# schematic.net
KiCad netlist of a schematic drawn in EAGLE
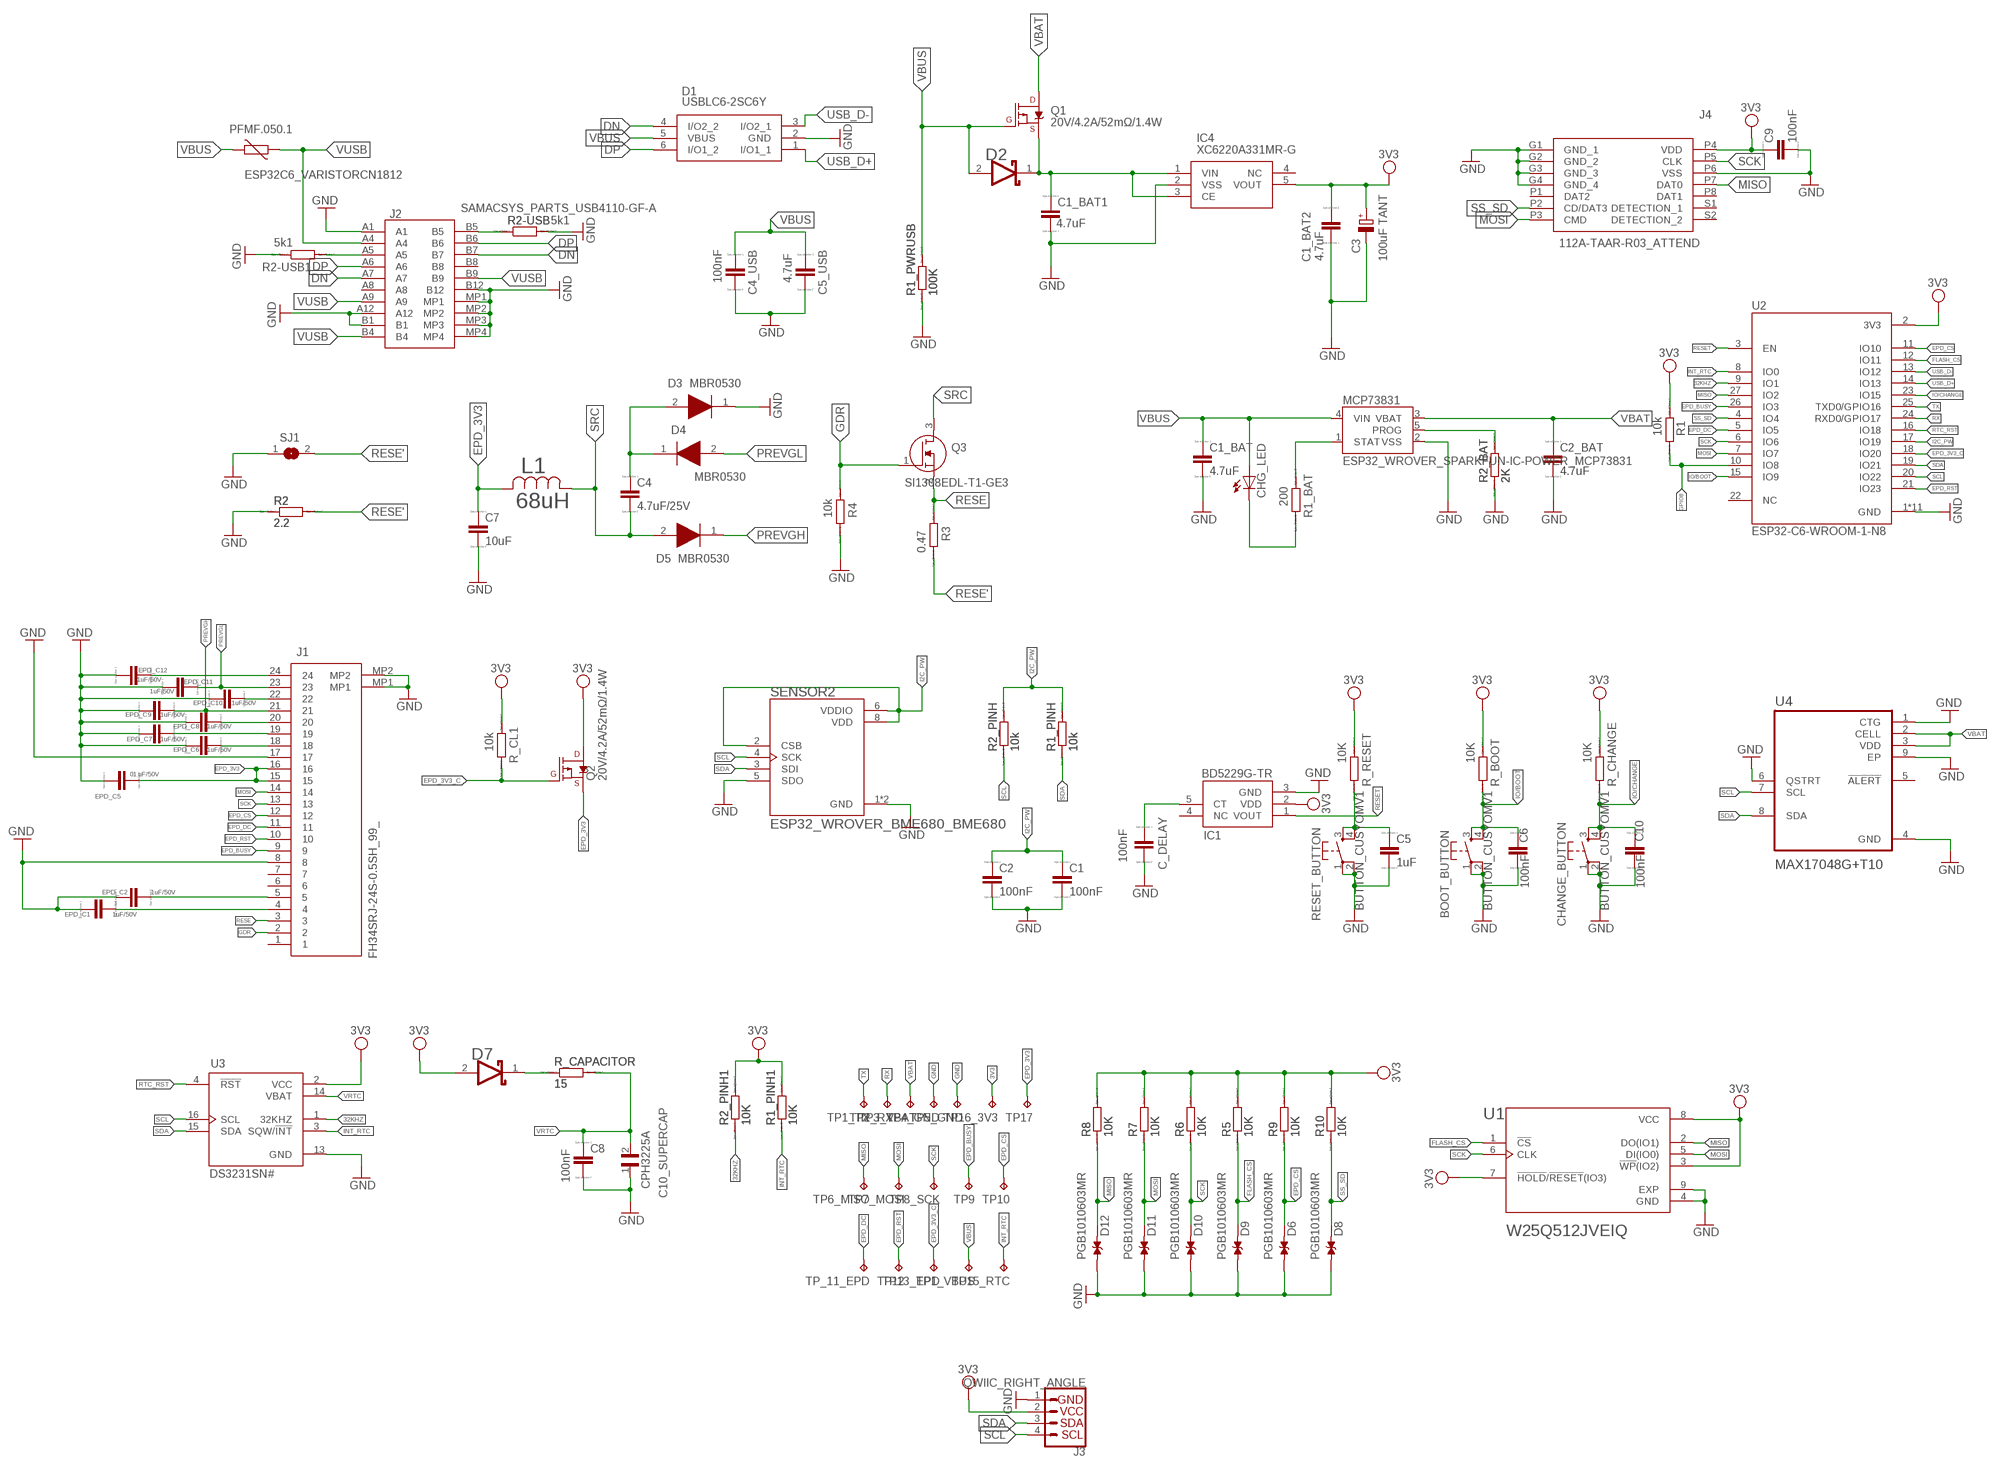
[diagram p0: schematic, sheet 1]

(export (version "E")
  (design (tool "Eeschema 10.0.6"))
  (components
    (comp (ref "BOOT_BUTTON")
      (value "BUTTON_CUSYOMV1")
      (footprint "eagle-import:MYBUTTON")
      (libsource (lib "eagle-import") (part "BUTTON_CUSYOMV1"))
    )
    (comp (ref "C1")
      (value "100nF")
      (footprint "eagle-import:EAGLE-LTSPICE_C0402")
      (libsource (lib "eagle-import") (part "EAGLE-LTSPICE_CC0402"))
    )
    (comp (ref "C1_BAT")
      (value "4.7uF")
      (footprint "eagle-import:EAGLE-LTSPICE_C0402")
      (libsource (lib "eagle-import") (part "EAGLE-LTSPICE_CC0402"))
    )
    (comp (ref "C1_BAT1")
      (value "4.7uF")
      (footprint "eagle-import:EAGLE-LTSPICE_C0402")
      (libsource (lib "eagle-import") (part "ESP32_WROVER_EAGLE-LTSPICE_CC0402"))
    )
    (comp (ref "C1_BAT2")
      (value "4.7uF")
      (footprint "eagle-import:EAGLE-LTSPICE_C0402")
      (libsource (lib "eagle-import") (part "ESP32_WROVER_EAGLE-LTSPICE_CC0402"))
    )
    (comp (ref "C2")
      (value "100nF")
      (footprint "eagle-import:EAGLE-LTSPICE_C0402")
      (libsource (lib "eagle-import") (part "EAGLE-LTSPICE_CC0402"))
    )
    (comp (ref "C2_BAT")
      (value "4.7uF")
      (footprint "eagle-import:EAGLE-LTSPICE_C0402")
      (libsource (lib "eagle-import") (part "EAGLE-LTSPICE_CC0402"))
    )
    (comp (ref "C3")
      (value "100uF TANT")
      (footprint "eagle-import:RCL_CT3528")
      (libsource (lib "eagle-import") (part "RCL_CPOL-EUCT3528"))
    )
    (comp (ref "C4")
      (value "4.7uF/25V")
      (footprint "eagle-import:EAGLE-LTSPICE_C0402")
      (libsource (lib "eagle-import") (part "EAGLE-LTSPICE_CC0402"))
    )
    (comp (ref "C4_USB")
      (value "100nF")
      (footprint "eagle-import:EAGLE-LTSPICE_C0402")
      (libsource (lib "eagle-import") (part "EAGLE-LTSPICE_CC0402"))
    )
    (comp (ref "C5")
      (value "1uF")
      (footprint "eagle-import:EAGLE-LTSPICE_C0402")
      (libsource (lib "eagle-import") (part "EAGLE-LTSPICE_CC0402"))
    )
    (comp (ref "C5_USB")
      (value "4.7uF")
      (footprint "eagle-import:EAGLE-LTSPICE_C0402")
      (libsource (lib "eagle-import") (part "EAGLE-LTSPICE_CC0402"))
    )
    (comp (ref "C6")
      (value "100nF")
      (footprint "eagle-import:EAGLE-LTSPICE_C0402")
      (libsource (lib "eagle-import") (part "EAGLE-LTSPICE_CC0402"))
    )
    (comp (ref "C7")
      (value "10uF")
      (footprint "eagle-import:EAGLE-LTSPICE_C0402")
      (libsource (lib "eagle-import") (part "EAGLE-LTSPICE_CC0402"))
    )
    (comp (ref "C8")
      (value "100nF")
      (footprint "eagle-import:EAGLE-LTSPICE_C0402")
      (libsource (lib "eagle-import") (part "EAGLE-LTSPICE_CC0402"))
    )
    (comp (ref "C9")
      (value "100nF")
      (footprint "eagle-import:EAGLE-LTSPICE_C0402")
      (libsource (lib "eagle-import") (part "EAGLE-LTSPICE_CC0402"))
    )
    (comp (ref "C10")
      (value "100nF")
      (footprint "eagle-import:EAGLE-LTSPICE_C0402")
      (libsource (lib "eagle-import") (part "EAGLE-LTSPICE_CC0402"))
    )
    (comp (ref "C10_SUPERCAP")
      (value "CPH3225A")
      (footprint "eagle-import:CAPCP3225X100N")
      (fields (field (name "MF") "Seiko Instruments"))
      (libsource (lib "eagle-import") (part "CPH3225A"))
    )
    (comp (ref "CHANGE_BUTTON")
      (value "BUTTON_CUSYOMV1")
      (footprint "eagle-import:MYBUTTON")
      (libsource (lib "eagle-import") (part "BUTTON_CUSYOMV1"))
    )
    (comp (ref "CHG_LED")
      (value "ADAFRUIT_LEDCHIP-LED0603")
      (footprint "eagle-import:ADAFRUIT_CHIP-LED0603")
      (libsource (lib "eagle-import") (part "ADAFRUIT_LEDCHIP-LED0603"))
    )
    (comp (ref "C_DELAY")
      (value "100nF")
      (footprint "eagle-import:EAGLE-LTSPICE_C0402")
      (libsource (lib "eagle-import") (part "EAGLE-LTSPICE_CC0402"))
    )
    (comp (ref "D1")
      (value "USBLC6-2SC6Y")
      (footprint "eagle-import:SOT95P280X145-6N")
      (fields (field (name "MF") "STMicroelectronics"))
      (libsource (lib "eagle-import") (part "USBLC6-2SC6Y"))
    )
    (comp (ref "D2")
      (value "ESP32_WROVER_AVX---SD0805S020S1R0_AVX_SD0805S020S1R0_0_0AVX_SD0805S020S1R0_0_0")
      (footprint "eagle-import:ESP32_WROVER_AVX---SD0805S020S1R0_AVX_SD0805S020S1R0_0")
      (fields
        (field (name "DIGIKEY_PART_NUMBER") "478-7800-1-ND")
        (field (name "MF") "AVX")
        (field (name "MOUSER_PART_NUMBER") "581-SD0805S020S1R0")
      )
      (libsource (lib "eagle-import") (part "ESP32_WROVER_AVX---SD0805S020S1R0_AVX_SD0805S020S1R0_0_0AVX_SD0805S020S1R0_0_0"))
    )
    (comp (ref "D3")
      (value "MBR0530")
      (footprint "eagle-import:SOD3716X135N")
      (fields (field (name "MF") "ON Semiconductor"))
      (libsource (lib "eagle-import") (part "MBR0530"))
    )
    (comp (ref "D4")
      (value "MBR0530")
      (footprint "eagle-import:SOD3716X135N")
      (fields (field (name "MF") "ON Semiconductor"))
      (libsource (lib "eagle-import") (part "MBR0530"))
    )
    (comp (ref "D5")
      (value "MBR0530")
      (footprint "eagle-import:SOD3716X135N")
      (fields (field (name "MF") "ON Semiconductor"))
      (libsource (lib "eagle-import") (part "MBR0530"))
    )
    (comp (ref "D6")
      (value "PGB1010603MR")
      (footprint "eagle-import:DIOC1608X36N")
      (fields (field (name "MF") "Littelfuse Inc."))
      (libsource (lib "eagle-import") (part "PGB1010603MR"))
    )
    (comp (ref "D7")
      (value "ESP32_WROVER_AVX---SD0805S020S1R0_AVX_SD0805S020S1R0_0_0AVX_SD0805S020S1R0_0_0")
      (footprint "eagle-import:ESP32_WROVER_AVX---SD0805S020S1R0_AVX_SD0805S020S1R0_0")
      (fields
        (field (name "DIGIKEY_PART_NUMBER") "478-7800-1-ND")
        (field (name "MF") "AVX")
        (field (name "MOUSER_PART_NUMBER") "581-SD0805S020S1R0")
      )
      (libsource (lib "eagle-import") (part "ESP32_WROVER_AVX---SD0805S020S1R0_AVX_SD0805S020S1R0_0_0AVX_SD0805S020S1R0_0_0"))
    )
    (comp (ref "D8")
      (value "PGB1010603MR")
      (footprint "eagle-import:DIOC1608X36N")
      (fields (field (name "MF") "Littelfuse Inc."))
      (libsource (lib "eagle-import") (part "PGB1010603MR"))
    )
    (comp (ref "D9")
      (value "PGB1010603MR")
      (footprint "eagle-import:DIOC1608X36N")
      (fields (field (name "MF") "Littelfuse Inc."))
      (libsource (lib "eagle-import") (part "PGB1010603MR"))
    )
    (comp (ref "D10")
      (value "PGB1010603MR")
      (footprint "eagle-import:DIOC1608X36N")
      (fields (field (name "MF") "Littelfuse Inc."))
      (libsource (lib "eagle-import") (part "PGB1010603MR"))
    )
    (comp (ref "D11")
      (value "PGB1010603MR")
      (footprint "eagle-import:DIOC1608X36N")
      (fields (field (name "MF") "Littelfuse Inc."))
      (libsource (lib "eagle-import") (part "PGB1010603MR"))
    )
    (comp (ref "D12")
      (value "PGB1010603MR")
      (footprint "eagle-import:DIOC1608X36N")
      (fields (field (name "MF") "Littelfuse Inc."))
      (libsource (lib "eagle-import") (part "PGB1010603MR"))
    )
    (comp (ref "EPD_C1")
      (value "1uF/50V")
      (footprint "eagle-import:EAGLE-LTSPICE_C0402")
      (libsource (lib "eagle-import") (part "EAGLE-LTSPICE_CC0402"))
    )
    (comp (ref "EPD_C2")
      (value "1uF/50V")
      (footprint "eagle-import:EAGLE-LTSPICE_C0402")
      (libsource (lib "eagle-import") (part "EAGLE-LTSPICE_CC0402"))
    )
    (comp (ref "EPD_C5")
      (value "01.uF/50V")
      (footprint "eagle-import:EAGLE-LTSPICE_C0402")
      (libsource (lib "eagle-import") (part "EAGLE-LTSPICE_CC0402"))
    )
    (comp (ref "EPD_C6")
      (value "1uF/50V")
      (footprint "eagle-import:EAGLE-LTSPICE_C0402")
      (libsource (lib "eagle-import") (part "EAGLE-LTSPICE_CC0402"))
    )
    (comp (ref "EPD_C7")
      (value "1uF/50V")
      (footprint "eagle-import:EAGLE-LTSPICE_C0402")
      (libsource (lib "eagle-import") (part "EAGLE-LTSPICE_CC0402"))
    )
    (comp (ref "EPD_C8")
      (value "1uF/50V")
      (footprint "eagle-import:EAGLE-LTSPICE_C0402")
      (libsource (lib "eagle-import") (part "EAGLE-LTSPICE_CC0402"))
    )
    (comp (ref "EPD_C9")
      (value "1uF/50V")
      (footprint "eagle-import:EAGLE-LTSPICE_C0402")
      (libsource (lib "eagle-import") (part "EAGLE-LTSPICE_CC0402"))
    )
    (comp (ref "EPD_C10")
      (value "1uF/50V")
      (footprint "eagle-import:EAGLE-LTSPICE_C0402")
      (libsource (lib "eagle-import") (part "EAGLE-LTSPICE_CC0402"))
    )
    (comp (ref "EPD_C11")
      (value "1uF/50V")
      (footprint "eagle-import:EAGLE-LTSPICE_C0402")
      (libsource (lib "eagle-import") (part "EAGLE-LTSPICE_CC0402"))
    )
    (comp (ref "EPD_C12")
      (value "1uF/50V")
      (footprint "eagle-import:EAGLE-LTSPICE_C0402")
      (libsource (lib "eagle-import") (part "EAGLE-LTSPICE_CC0402"))
    )
    (comp (ref "IC1")
      (value "BD5229G-TR")
      (footprint "eagle-import:SOT95P280X125-5N")
      (fields (field (name "MOUSER_PART_NUMBER") "755-BD5229G-TR"))
      (libsource (lib "eagle-import") (part "BD5229G-TR"))
    )
    (comp (ref "IC4")
      (value "XC6220A331MR-G")
      (footprint "eagle-import:SOT95P280X120-5N")
      (fields (field (name "MOUSER_PART_NUMBER") "865-XC6220A331MR-G"))
      (libsource (lib "eagle-import") (part "XC6220A331MR-G"))
    )
    (comp (ref "J1")
      (value "FH34SRJ-24S-0.5SH_99_")
      (footprint "eagle-import:FH34SRJ24S05SH99")
      (fields
        (field (name "MANUFACTURER_PART_NUMBER") "FH34SRJ-24S-0.5SH(99)")
        (field (name "MOUSER_PART_NUMBER") "798-FH34SRJ24S05SH99")
      )
      (libsource (lib "eagle-import") (part "FH34SRJ-24S-0.5SH_99_"))
    )
    (comp (ref "J2")
      (value "SAMACSYS_PARTS_USB4110-GF-A")
      (footprint "eagle-import:SAMACSYS_PARTS_USB4110GFA")
      (fields
        (field (name "MANUFACTURER_PART_NUMBER") "USB4110-GF-A")
        (field (name "MOUSER_PART_NUMBER") "640-USB4110-GF-A")
      )
      (libsource (lib "eagle-import") (part "SAMACSYS_PARTS_USB4110-GF-A"))
    )
    (comp (ref "J3")
      (value "QWIIC_RIGHT_ANGLE")
      (footprint "eagle-import:JST04_1MM_RA")
      (libsource (lib "eagle-import") (part "QWIIC_CONNECTORJS-1MM"))
    )
    (comp (ref "J4")
      (value "112A-TAAR-R03_ATTEND")
      (footprint "eagle-import:112ATAARR03ATTEND")
      (fields (field (name "MANUFACTURER_PART_NUMBER") "112A-TAAR-R03 ATTEND"))
      (libsource (lib "eagle-import") (part "112A-TAAR-R03_ATTEND"))
    )
    (comp (ref "L1")
      (value "68uH")
      (footprint "eagle-import:IND_4828-WE-TPC_WRE")
      (fields
        (field (name "MANUFACTURER_PART_NUMBER") "744043680")
        (field (name "COPYRIGHT") "Copyright (C) 2024 Ultra Librarian. All rights reserved.")
      )
      (libsource (lib "eagle-import") (part "744043680IND_4828-WE-TPC_WRE"))
    )
    (comp (ref "MCP73831")
      (value "ESP32_WROVER_SPARKFUN-IC-POWER_MCP73831")
      (footprint "eagle-import:ESP32_WROVER_SPARKFUN-IC-POWER_SOT23-5")
      (libsource (lib "eagle-import") (part "ESP32_WROVER_SPARKFUN-IC-POWER_MCP73831"))
    )
    (comp (ref "PFMF.050.1")
      (value "ESP32C6_VARISTORCN1812")
      (footprint "eagle-import:ESP32C6_VARISTOR_CT_CN1812")
      (libsource (lib "eagle-import") (part "ESP32C6_VARISTORCN1812"))
    )
    (comp (ref "Q1")
      (value "20V/4.2A/52mΩ/1.4W")
      (footprint "eagle-import:ESP32_WROVER_SPARKFUN-DISCRETESEMI_SOT23-3")
      (libsource (lib "eagle-import") (part "ESP32_WROVER_SPARKFUN-DISCRETESEMI_MOSFET_PCH-DMG2305UX-7"))
    )
    (comp (ref "Q2")
      (value "20V/4.2A/52mΩ/1.4W")
      (footprint "eagle-import:ESP32_WROVER_SPARKFUN-DISCRETESEMI_SOT23-3")
      (libsource (lib "eagle-import") (part "ESP32_WROVER_SPARKFUN-DISCRETESEMI_MOSFET_PCH-DMG2305UX-7"))
    )
    (comp (ref "Q3")
      (value "SI1308EDL-T1-GE3")
      (footprint "eagle-import:SOT65P210X110-3N")
      (fields (field (name "MF") "Vishay Siliconix"))
      (libsource (lib "eagle-import") (part "SI1308EDL-T1-GE3"))
    )
    (comp (ref "R1")
      (value "10k")
      (footprint "eagle-import:ESP32_WROVER_EAGLE-LTSPICE_R0402")
      (libsource (lib "eagle-import") (part "ESP32_WROVER_EAGLE-LTSPICE_RR0402"))
    )
    (comp (ref "R1_BAT")
      (value "200")
      (footprint "eagle-import:ESP32_WROVER_EAGLE-LTSPICE_R0402")
      (libsource (lib "eagle-import") (part "ESP32_WROVER_EAGLE-LTSPICE_RR0402"))
    )
    (comp (ref "R1_PINH")
      (value "10k")
      (footprint "eagle-import:ESP32_WROVER_EAGLE-LTSPICE_R0402")
      (libsource (lib "eagle-import") (part "ESP32_WROVER_EAGLE-LTSPICE_RR0402"))
    )
    (comp (ref "R1_PINH1")
      (value "10K")
      (footprint "eagle-import:ESP32_WROVER_EAGLE-LTSPICE_R0402")
      (libsource (lib "eagle-import") (part "ESP32_WROVER_EAGLE-LTSPICE_RR0402"))
    )
    (comp (ref "R1_PWRUSB")
      (value "100K")
      (footprint "eagle-import:ESP32_WROVER_EAGLE-LTSPICE_R0402")
      (libsource (lib "eagle-import") (part "ESP32_WROVER_EAGLE-LTSPICE_RR0402"))
    )
    (comp (ref "R2")
      (value "2.2")
      (footprint "eagle-import:ESP32_WROVER_EAGLE-LTSPICE_R0402")
      (libsource (lib "eagle-import") (part "ESP32_WROVER_EAGLE-LTSPICE_RR0402"))
    )
    (comp (ref "R2-USB")
      (value "5k1")
      (footprint "eagle-import:ESP32_WROVER_EAGLE-LTSPICE_R0402")
      (libsource (lib "eagle-import") (part "ESP32_WROVER_EAGLE-LTSPICE_RR0402"))
    )
    (comp (ref "R2-USB1")
      (value "5k1")
      (footprint "eagle-import:ESP32_WROVER_EAGLE-LTSPICE_R0402")
      (libsource (lib "eagle-import") (part "ESP32_WROVER_EAGLE-LTSPICE_RR0402"))
    )
    (comp (ref "R2_BAT")
      (value "2K")
      (footprint "eagle-import:ESP32_WROVER_EAGLE-LTSPICE_R0402")
      (libsource (lib "eagle-import") (part "ESP32_WROVER_EAGLE-LTSPICE_RR0402"))
    )
    (comp (ref "R2_PINH")
      (value "10k")
      (footprint "eagle-import:ESP32_WROVER_EAGLE-LTSPICE_R0402")
      (libsource (lib "eagle-import") (part "ESP32_WROVER_EAGLE-LTSPICE_RR0402"))
    )
    (comp (ref "R2_PINH1")
      (value "10K")
      (footprint "eagle-import:ESP32_WROVER_EAGLE-LTSPICE_R0402")
      (libsource (lib "eagle-import") (part "ESP32_WROVER_EAGLE-LTSPICE_RR0402"))
    )
    (comp (ref "R3")
      (value "0.47")
      (footprint "eagle-import:ESP32_WROVER_EAGLE-LTSPICE_R0402")
      (libsource (lib "eagle-import") (part "ESP32_WROVER_EAGLE-LTSPICE_RR0402"))
    )
    (comp (ref "R4")
      (value "10k")
      (footprint "eagle-import:ESP32_WROVER_EAGLE-LTSPICE_R0402")
      (libsource (lib "eagle-import") (part "ESP32_WROVER_EAGLE-LTSPICE_RR0402"))
    )
    (comp (ref "R5")
      (value "10K")
      (footprint "eagle-import:ESP32_WROVER_EAGLE-LTSPICE_R0402")
      (libsource (lib "eagle-import") (part "ESP32_WROVER_EAGLE-LTSPICE_RR0402"))
    )
    (comp (ref "R6")
      (value "10K")
      (footprint "eagle-import:ESP32_WROVER_EAGLE-LTSPICE_R0402")
      (libsource (lib "eagle-import") (part "ESP32_WROVER_EAGLE-LTSPICE_RR0402"))
    )
    (comp (ref "R7")
      (value "10K")
      (footprint "eagle-import:ESP32_WROVER_EAGLE-LTSPICE_R0402")
      (libsource (lib "eagle-import") (part "ESP32_WROVER_EAGLE-LTSPICE_RR0402"))
    )
    (comp (ref "R8")
      (value "10K")
      (footprint "eagle-import:ESP32_WROVER_EAGLE-LTSPICE_R0402")
      (libsource (lib "eagle-import") (part "ESP32_WROVER_EAGLE-LTSPICE_RR0402"))
    )
    (comp (ref "R9")
      (value "10K")
      (footprint "eagle-import:ESP32_WROVER_EAGLE-LTSPICE_R0402")
      (libsource (lib "eagle-import") (part "ESP32_WROVER_EAGLE-LTSPICE_RR0402"))
    )
    (comp (ref "R10")
      (value "10K")
      (footprint "eagle-import:ESP32_WROVER_EAGLE-LTSPICE_R0402")
      (libsource (lib "eagle-import") (part "ESP32_WROVER_EAGLE-LTSPICE_RR0402"))
    )
    (comp (ref "RESET_BUTTON")
      (value "BUTTON_CUSYOMV1")
      (footprint "eagle-import:MYBUTTON")
      (libsource (lib "eagle-import") (part "BUTTON_CUSYOMV1"))
    )
    (comp (ref "R_BOOT")
      (value "10K")
      (footprint "eagle-import:ESP32_WROVER_EAGLE-LTSPICE_R0402")
      (libsource (lib "eagle-import") (part "ESP32_WROVER_EAGLE-LTSPICE_RR0402"))
    )
    (comp (ref "R_CAPACITOR")
      (value "15")
      (footprint "eagle-import:ESP32_WROVER_EAGLE-LTSPICE_R0402")
      (libsource (lib "eagle-import") (part "ESP32_WROVER_EAGLE-LTSPICE_RR0402"))
    )
    (comp (ref "R_CHANGE")
      (value "10K")
      (footprint "eagle-import:ESP32_WROVER_EAGLE-LTSPICE_R0402")
      (libsource (lib "eagle-import") (part "ESP32_WROVER_EAGLE-LTSPICE_RR0402"))
    )
    (comp (ref "R_CL1")
      (value "10k")
      (footprint "eagle-import:ESP32_WROVER_EAGLE-LTSPICE_R0402")
      (libsource (lib "eagle-import") (part "ESP32_WROVER_EAGLE-LTSPICE_RR0402"))
    )
    (comp (ref "R_RESET")
      (value "10K")
      (footprint "eagle-import:ESP32_WROVER_EAGLE-LTSPICE_R0402")
      (libsource (lib "eagle-import") (part "ESP32_WROVER_EAGLE-LTSPICE_RR0402"))
    )
    (comp (ref "SENSOR2")
      (value "ESP32_WROVER_BME680_BME680")
      (footprint "eagle-import:ESP32_WROVER_BME680_PSON80P300X300X100-8N")
      (fields (field (name "MF") "Bosch Sensortec") (field (name "MP") "BME680"))
      (libsource (lib "eagle-import") (part "ESP32_WROVER_BME680_BME680"))
    )
    (comp (ref "SJ1") (value "SJ") (footprint "eagle-import:SJ") (libsource (lib "eagle-import") (part "SJ")))
    (comp (ref "TP1_TX")
      (value "TPTP20R")
      (footprint "eagle-import:TP20R")
      (libsource (lib "eagle-import") (part "TPTP20R"))
    )
    (comp (ref "TP1_VBUS")
      (value "TPTP20R")
      (footprint "eagle-import:TP20R")
      (libsource (lib "eagle-import") (part "TPTP20R"))
    )
    (comp (ref "TP2_RX")
      (value "TPTP20R")
      (footprint "eagle-import:TP20R")
      (libsource (lib "eagle-import") (part "TPTP20R"))
    )
    (comp (ref "TP3_VBAT")
      (value "TPTP20R")
      (footprint "eagle-import:TP20R")
      (libsource (lib "eagle-import") (part "TPTP20R"))
    )
    (comp (ref "TP4_GND")
      (value "TPTP20R")
      (footprint "eagle-import:TP20R")
      (libsource (lib "eagle-import") (part "TPTP20R"))
    )
    (comp (ref "TP5_GND")
      (value "TPTP20R")
      (footprint "eagle-import:TP20R")
      (libsource (lib "eagle-import") (part "TPTP20R"))
    )
    (comp (ref "TP6_MISO")
      (value "TPTP20R")
      (footprint "eagle-import:TP20R")
      (libsource (lib "eagle-import") (part "TPTP20R"))
    )
    (comp (ref "TP7_MOSI")
      (value "TPTP20R")
      (footprint "eagle-import:TP20R")
      (libsource (lib "eagle-import") (part "TPTP20R"))
    )
    (comp (ref "TP8_SCK")
      (value "TPTP20R")
      (footprint "eagle-import:TP20R")
      (libsource (lib "eagle-import") (part "TPTP20R"))
    )
    (comp (ref "TP9")
      (value "TPTP20R")
      (footprint "eagle-import:TP20R")
      (libsource (lib "eagle-import") (part "TPTP20R"))
    )
    (comp (ref "TP10")
      (value "TPTP20R")
      (footprint "eagle-import:TP20R")
      (libsource (lib "eagle-import") (part "TPTP20R"))
    )
    (comp (ref "TP12")
      (value "TPTP20R")
      (footprint "eagle-import:TP20R")
      (libsource (lib "eagle-import") (part "TPTP20R"))
    )
    (comp (ref "TP13_EPD")
      (value "TPTP20R")
      (footprint "eagle-import:TP20R")
      (libsource (lib "eagle-import") (part "TPTP20R"))
    )
    (comp (ref "TP15_RTC")
      (value "TPTP20R")
      (footprint "eagle-import:TP20R")
      (libsource (lib "eagle-import") (part "TPTP20R"))
    )
    (comp (ref "TP16_3V3")
      (value "TPTP20R")
      (footprint "eagle-import:TP20R")
      (libsource (lib "eagle-import") (part "TPTP20R"))
    )
    (comp (ref "TP17")
      (value "TPTP20R")
      (footprint "eagle-import:TP20R")
      (libsource (lib "eagle-import") (part "TPTP20R"))
    )
    (comp (ref "TP_11_EPD")
      (value "TPTP20R")
      (footprint "eagle-import:TP20R")
      (libsource (lib "eagle-import") (part "TPTP20R"))
    )
    (comp (ref "U1")
      (value "W25Q512JVEIQ")
      (footprint "eagle-import:SON127P600X800X80-9N")
      (fields (field (name "MF") "Winbond Electronics"))
      (libsource (lib "eagle-import") (part "W25Q512JVEIQ"))
    )
    (comp (ref "U2")
      (value "ESP32-C6-WROOM-1-N8")
      (footprint "eagle-import:XCVR_ESP32-C6-WROOM-1-N8")
      (fields (field (name "MF") "Espressif Systems"))
      (libsource (lib "eagle-import") (part "ESP32-C6-WROOM-1-N8"))
    )
    (comp (ref "U3")
      (value "DS3231SN#")
      (footprint "eagle-import:SOIC127P1032X265-16N")
      (fields (field (name "MF") "Analog Devices"))
      (libsource (lib "eagle-import") (part "DS3231SN#"))
    )
    (comp (ref "U4")
      (value "MAX17048G+T10")
      (footprint "eagle-import:SON50P200X200X80-9N")
      (fields (field (name "MF") "Analog Devices"))
      (libsource (lib "eagle-import") (part "MAX17048G+T10"))
    )
  )
  (nets
    (net (code "1") (name "3V3") (class "Default")
      (node (ref "C1_BAT2") (pin "2") (pinfunction "2_2") (pintype "passive"))
      (node (ref "C3") (pin "+") (pinfunction "+_+") (pintype "passive"))
      (node (ref "C9") (pin "1") (pinfunction "1_1") (pintype "passive"))
      (node (ref "D7") (pin "2") (pinfunction "ANODE_2") (pintype "bidirectional"))
      (node (ref "IC1") (pin "2") (pinfunction "VDD_2") (pintype "bidirectional"))
      (node (ref "IC4") (pin "5") (pinfunction "VOUT_5") (pintype "bidirectional"))
      (node (ref "J3") (pin "2") (pinfunction "2_2") (pintype "power_in"))
      (node (ref "J4") (pin "P4") (pinfunction "VDD_P4") (pintype "bidirectional"))
      (node (ref "Q2") (pin "3") (pinfunction "D_3") (pintype "bidirectional"))
      (node (ref "R1") (pin "2") (pinfunction "2_2") (pintype "passive"))
      (node (ref "R10") (pin "2") (pinfunction "2_2") (pintype "passive"))
      (node (ref "R1_PINH1") (pin "2") (pinfunction "2_2") (pintype "passive"))
      (node (ref "R2_PINH1") (pin "2") (pinfunction "2_2") (pintype "passive"))
      (node (ref "R5") (pin "2") (pinfunction "2_2") (pintype "passive"))
      (node (ref "R6") (pin "2") (pinfunction "2_2") (pintype "passive"))
      (node (ref "R7") (pin "2") (pinfunction "2_2") (pintype "passive"))
      (node (ref "R8") (pin "2") (pinfunction "2_2") (pintype "passive"))
      (node (ref "R9") (pin "2") (pinfunction "2_2") (pintype "passive"))
      (node (ref "R_BOOT") (pin "2") (pinfunction "2_2") (pintype "passive"))
      (node (ref "R_CHANGE") (pin "2") (pinfunction "2_2") (pintype "passive"))
      (node (ref "R_CL1") (pin "2") (pinfunction "2_2") (pintype "passive"))
      (node (ref "R_RESET") (pin "2") (pinfunction "2_2") (pintype "passive"))
      (node (ref "TP16_3V3") (pin "TP") (pinfunction "TP_TP") (pintype "input"))
      (node (ref "U1") (pin "3") (pinfunction "~{WP}(IO2)_3") (pintype "bidirectional"))
      (node (ref "U1") (pin "7") (pinfunction "~{HOLD}/~{RESET}(IO3)_7") (pintype "bidirectional"))
      (node (ref "U1") (pin "8") (pinfunction "VCC_8") (pintype "power_in"))
      (node (ref "U2") (pin "2") (pinfunction "3V3_2") (pintype "power_in"))
      (node (ref "U3") (pin "2") (pinfunction "VCC_2") (pintype "power_in"))
    )
    (net (code "2") (name "32KHZ") (class "Default")
      (node (ref "R2_PINH1") (pin "1") (pinfunction "1_1") (pintype "passive"))
      (node (ref "U2") (pin "9") (pinfunction "IO1_9") (pintype "bidirectional"))
      (node (ref "U3") (pin "1") (pinfunction "32KHZ_1") (pintype "output"))
    )
    (net (code "3") (name "DN") (class "Default")
      (node (ref "D1") (pin "4") (pinfunction "I/O2_2_4") (pintype "bidirectional"))
      (node (ref "J2") (pin "A7") (pinfunction "A7_A7") (pintype "bidirectional"))
      (node (ref "J2") (pin "B7") (pinfunction "B7_B7") (pintype "bidirectional"))
    )
    (net (code "4") (name "DP") (class "Default")
      (node (ref "D1") (pin "6") (pinfunction "I/O1_2_6") (pintype "bidirectional"))
      (node (ref "J2") (pin "A6") (pinfunction "A6_A6") (pintype "bidirectional"))
      (node (ref "J2") (pin "B6") (pinfunction "B6_B6") (pintype "bidirectional"))
    )
    (net (code "5") (name "EPD_3V3") (class "Default")
      (node (ref "C7") (pin "1") (pinfunction "1_1") (pintype "passive"))
      (node (ref "EPD_C5") (pin "2") (pinfunction "2_2") (pintype "passive"))
      (node (ref "J1") (pin "15") (pinfunction "15_15") (pintype "bidirectional"))
      (node (ref "J1") (pin "16") (pinfunction "16_16") (pintype "bidirectional"))
      (node (ref "L1") (pin "2") (pinfunction "2_2") (pintype "passive"))
      (node (ref "Q2") (pin "2") (pinfunction "S_2") (pintype "bidirectional"))
      (node (ref "TP17") (pin "TP") (pinfunction "TP_TP") (pintype "input"))
    )
    (net (code "6") (name "EPD_3V3_C") (class "Default")
      (node (ref "Q2") (pin "1") (pinfunction "G_1") (pintype "bidirectional"))
      (node (ref "R_CL1") (pin "1") (pinfunction "1_1") (pintype "passive"))
      (node (ref "TP13_EPD") (pin "TP") (pinfunction "TP_TP") (pintype "input"))
      (node (ref "U2") (pin "18") (pinfunction "IO20_18") (pintype "bidirectional"))
    )
    (net (code "7") (name "EPD_BUSY") (class "Default")
      (node (ref "J1") (pin "9") (pinfunction "9_9") (pintype "bidirectional"))
      (node (ref "TP9") (pin "TP") (pinfunction "TP_TP") (pintype "input"))
      (node (ref "U2") (pin "26") (pinfunction "IO3_26") (pintype "bidirectional"))
    )
    (net (code "8") (name "EPD_CS") (class "Default")
      (node (ref "D6") (pin "2") (pinfunction "2_2") (pintype "passive"))
      (node (ref "J1") (pin "12") (pinfunction "12_12") (pintype "bidirectional"))
      (node (ref "R9") (pin "1") (pinfunction "1_1") (pintype "passive"))
      (node (ref "TP10") (pin "TP") (pinfunction "TP_TP") (pintype "input"))
      (node (ref "U2") (pin "11") (pinfunction "IO10_11") (pintype "bidirectional"))
    )
    (net (code "9") (name "EPD_DC") (class "Default")
      (node (ref "J1") (pin "11") (pinfunction "11_11") (pintype "bidirectional"))
      (node (ref "TP_11_EPD") (pin "TP") (pinfunction "TP_TP") (pintype "input"))
      (node (ref "U2") (pin "5") (pinfunction "IO5_5") (pintype "bidirectional"))
    )
    (net (code "10") (name "EPD_RST") (class "Default")
      (node (ref "J1") (pin "10") (pinfunction "10_10") (pintype "bidirectional"))
      (node (ref "TP12") (pin "TP") (pinfunction "TP_TP") (pintype "input"))
      (node (ref "U2") (pin "21") (pinfunction "IO23_21") (pintype "bidirectional"))
    )
    (net (code "11") (name "FLASH_CS") (class "Default")
      (node (ref "D9") (pin "2") (pinfunction "2_2") (pintype "passive"))
      (node (ref "R5") (pin "1") (pinfunction "1_1") (pintype "passive"))
      (node (ref "U1") (pin "1") (pinfunction "~{CS}_1") (pintype "input"))
      (node (ref "U2") (pin "12") (pinfunction "IO11_12") (pintype "bidirectional"))
    )
    (net (code "12") (name "GDR") (class "Default")
      (node (ref "J1") (pin "2") (pinfunction "2_2") (pintype "bidirectional"))
      (node (ref "Q3") (pin "1") (pinfunction "G_1") (pintype "bidirectional"))
      (node (ref "R4") (pin "2") (pinfunction "2_2") (pintype "passive"))
    )
    (net (code "13") (name "GND") (class "Default")
      (node (ref "BOOT_BUTTON") (pin "1") (pinfunction "1_1") (pintype "passive"))
      (node (ref "BOOT_BUTTON") (pin "2") (pinfunction "2_2") (pintype "passive"))
      (node (ref "C1") (pin "2") (pinfunction "2_2") (pintype "passive"))
      (node (ref "C10") (pin "2") (pinfunction "2_2") (pintype "passive"))
      (node (ref "C10_SUPERCAP") (pin "1") (pinfunction "1_1") (pintype "passive"))
      (node (ref "C1_BAT") (pin "2") (pinfunction "2_2") (pintype "passive"))
      (node (ref "C1_BAT1") (pin "1") (pinfunction "1_1") (pintype "passive"))
      (node (ref "C1_BAT2") (pin "1") (pinfunction "1_1") (pintype "passive"))
      (node (ref "C2") (pin "2") (pinfunction "2_2") (pintype "passive"))
      (node (ref "C2_BAT") (pin "2") (pinfunction "2_2") (pintype "passive"))
      (node (ref "C3") (pin "-") (pinfunction "-_-") (pintype "passive"))
      (node (ref "C4_USB") (pin "2") (pinfunction "2_2") (pintype "passive"))
      (node (ref "C5") (pin "2") (pinfunction "2_2") (pintype "passive"))
      (node (ref "C5_USB") (pin "2") (pinfunction "2_2") (pintype "passive"))
      (node (ref "C6") (pin "2") (pinfunction "2_2") (pintype "passive"))
      (node (ref "C7") (pin "2") (pinfunction "2_2") (pintype "passive"))
      (node (ref "C8") (pin "2") (pinfunction "2_2") (pintype "passive"))
      (node (ref "C9") (pin "2") (pinfunction "2_2") (pintype "passive"))
      (node (ref "CHANGE_BUTTON") (pin "1") (pinfunction "1_1") (pintype "passive"))
      (node (ref "CHANGE_BUTTON") (pin "2") (pinfunction "2_2") (pintype "passive"))
      (node (ref "C_DELAY") (pin "2") (pinfunction "2_2") (pintype "passive"))
      (node (ref "D1") (pin "2") (pinfunction "GND_2") (pintype "bidirectional"))
      (node (ref "D10") (pin "1") (pinfunction "1_1") (pintype "passive"))
      (node (ref "D11") (pin "1") (pinfunction "1_1") (pintype "passive"))
      (node (ref "D12") (pin "1") (pinfunction "1_1") (pintype "passive"))
      (node (ref "D3") (pin "1") (pinfunction "K_1") (pintype "bidirectional"))
      (node (ref "D6") (pin "1") (pinfunction "1_1") (pintype "passive"))
      (node (ref "D8") (pin "1") (pinfunction "1_1") (pintype "passive"))
      (node (ref "D9") (pin "1") (pinfunction "1_1") (pintype "passive"))
      (node (ref "EPD_C1") (pin "1") (pinfunction "1_1") (pintype "passive"))
      (node (ref "EPD_C10") (pin "1") (pinfunction "1_1") (pintype "passive"))
      (node (ref "EPD_C11") (pin "1") (pinfunction "1_1") (pintype "passive"))
      (node (ref "EPD_C12") (pin "1") (pinfunction "1_1") (pintype "passive"))
      (node (ref "EPD_C2") (pin "1") (pinfunction "1_1") (pintype "passive"))
      (node (ref "EPD_C5") (pin "1") (pinfunction "1_1") (pintype "passive"))
      (node (ref "EPD_C6") (pin "1") (pinfunction "1_1") (pintype "passive"))
      (node (ref "EPD_C7") (pin "1") (pinfunction "1_1") (pintype "passive"))
      (node (ref "EPD_C8") (pin "1") (pinfunction "1_1") (pintype "passive"))
      (node (ref "EPD_C9") (pin "1") (pinfunction "1_1") (pintype "passive"))
      (node (ref "IC1") (pin "3") (pinfunction "GND_3") (pintype "bidirectional"))
      (node (ref "IC4") (pin "2") (pinfunction "VSS_2") (pintype "bidirectional"))
      (node (ref "J1") (pin "17") (pinfunction "17_17") (pintype "bidirectional"))
      (node (ref "J1") (pin "8") (pinfunction "8_8") (pintype "bidirectional"))
      (node (ref "J1") (pin "MP1") (pinfunction "MP1_MP1") (pintype "bidirectional"))
      (node (ref "J1") (pin "MP2") (pinfunction "MP2_MP2") (pintype "bidirectional"))
      (node (ref "J2") (pin "A1") (pinfunction "A1_A1") (pintype "bidirectional"))
      (node (ref "J2") (pin "A12") (pinfunction "A12_A12") (pintype "bidirectional"))
      (node (ref "J2") (pin "B1") (pinfunction "B1_B1") (pintype "bidirectional"))
      (node (ref "J2") (pin "B12") (pinfunction "B12_B12") (pintype "bidirectional"))
      (node (ref "J2") (pin "MP1") (pinfunction "MP1_MP1") (pintype "bidirectional"))
      (node (ref "J2") (pin "MP2") (pinfunction "MP2_MP2") (pintype "bidirectional"))
      (node (ref "J2") (pin "MP3") (pinfunction "MP3_MP3") (pintype "bidirectional"))
      (node (ref "J2") (pin "MP4") (pinfunction "MP4_MP4") (pintype "bidirectional"))
      (node (ref "J3") (pin "1") (pinfunction "1_1") (pintype "power_in"))
      (node (ref "J4") (pin "G1") (pinfunction "GND_1_G1") (pintype "bidirectional"))
      (node (ref "J4") (pin "G2") (pinfunction "GND_2_G2") (pintype "bidirectional"))
      (node (ref "J4") (pin "G3") (pinfunction "GND_3_G3") (pintype "bidirectional"))
      (node (ref "J4") (pin "G4") (pinfunction "GND_4_G4") (pintype "bidirectional"))
      (node (ref "J4") (pin "P6") (pinfunction "VSS_P6") (pintype "bidirectional"))
      (node (ref "MCP73831") (pin "2") (pinfunction "VSS_2") (pintype "power_in"))
      (node (ref "R1_PWRUSB") (pin "1") (pinfunction "1_1") (pintype "passive"))
      (node (ref "R2") (pin "1") (pinfunction "1_1") (pintype "passive"))
      (node (ref "R2-USB") (pin "2") (pinfunction "2_2") (pintype "passive"))
      (node (ref "R2-USB1") (pin "1") (pinfunction "1_1") (pintype "passive"))
      (node (ref "R2_BAT") (pin "1") (pinfunction "1_1") (pintype "passive"))
      (node (ref "R4") (pin "1") (pinfunction "1_1") (pintype "passive"))
      (node (ref "RESET_BUTTON") (pin "1") (pinfunction "1_1") (pintype "passive"))
      (node (ref "RESET_BUTTON") (pin "2") (pinfunction "2_2") (pintype "passive"))
      (node (ref "SENSOR2") (pin "1") (pinfunction "GND_1") (pintype "power_in"))
      (node (ref "SENSOR2") (pin "5") (pinfunction "SDO_5") (pintype "bidirectional"))
      (node (ref "SENSOR2") (pin "7") (pinfunction "GND_7") (pintype "power_in"))
      (node (ref "SJ1") (pin "1") (pinfunction "1_1") (pintype "passive"))
      (node (ref "TP4_GND") (pin "TP") (pinfunction "TP_TP") (pintype "input"))
      (node (ref "TP5_GND") (pin "TP") (pinfunction "TP_TP") (pintype "input"))
      (node (ref "U1") (pin "4") (pinfunction "GND_4") (pintype "power_in"))
      (node (ref "U1") (pin "9") (pinfunction "EXP_9") (pintype "passive"))
      (node (ref "U2") (pin "1") (pinfunction "GND_1") (pintype "power_in"))
      (node (ref "U2") (pin "28") (pinfunction "GND_28") (pintype "power_in"))
      (node (ref "U2") (pin "29_1") (pinfunction "GND_29_1") (pintype "power_in"))
      (node (ref "U2") (pin "29_2") (pinfunction "GND_29_2") (pintype "power_in"))
      (node (ref "U2") (pin "29_3") (pinfunction "GND_29_3") (pintype "power_in"))
      (node (ref "U2") (pin "29_4") (pinfunction "GND_29_4") (pintype "power_in"))
      (node (ref "U2") (pin "29_5") (pinfunction "GND_29_5") (pintype "power_in"))
      (node (ref "U2") (pin "29_6") (pinfunction "GND_29_6") (pintype "power_in"))
      (node (ref "U2") (pin "29_7") (pinfunction "GND_29_7") (pintype "power_in"))
      (node (ref "U2") (pin "29_8") (pinfunction "GND_29_8") (pintype "power_in"))
      (node (ref "U2") (pin "29_9") (pinfunction "GND_29_9") (pintype "power_in"))
      (node (ref "U3") (pin "13") (pinfunction "GND_13") (pintype "power_in"))
      (node (ref "U4") (pin "1") (pinfunction "CTG_1") (pintype "power_in"))
      (node (ref "U4") (pin "4") (pinfunction "GND_4") (pintype "power_in"))
      (node (ref "U4") (pin "6") (pinfunction "QSTRT_6") (pintype "input"))
      (node (ref "U4") (pin "9") (pinfunction "EP_9") (pintype "power_in"))
    )
    (net (code "14") (name "GPIO8") (class "Default")
      (node (ref "R1") (pin "1") (pinfunction "1_1") (pintype "passive"))
      (node (ref "U2") (pin "10") (pinfunction "IO8_10") (pintype "bidirectional"))
    )
    (net (code "15") (name "I2C_PW") (class "Default")
      (node (ref "C1") (pin "1") (pinfunction "1_1") (pintype "passive"))
      (node (ref "C2") (pin "1") (pinfunction "1_1") (pintype "passive"))
      (node (ref "R1_PINH") (pin "2") (pinfunction "2_2") (pintype "passive"))
      (node (ref "R2_PINH") (pin "2") (pinfunction "2_2") (pintype "passive"))
      (node (ref "SENSOR2") (pin "2") (pinfunction "CSB_2") (pintype "input"))
      (node (ref "SENSOR2") (pin "6") (pinfunction "VDDIO_6") (pintype "power_in"))
      (node (ref "SENSOR2") (pin "8") (pinfunction "VDD_8") (pintype "power_in"))
      (node (ref "U2") (pin "17") (pinfunction "IO19_17") (pintype "bidirectional"))
    )
    (net (code "16") (name "INT_RTC") (class "Default")
      (node (ref "R1_PINH1") (pin "1") (pinfunction "1_1") (pintype "passive"))
      (node (ref "TP15_RTC") (pin "TP") (pinfunction "TP_TP") (pintype "input"))
      (node (ref "U2") (pin "8") (pinfunction "IO0_8") (pintype "bidirectional"))
      (node (ref "U3") (pin "3") (pinfunction "SQW/~{INT}_3") (pintype "output"))
    )
    (net (code "17") (name "IO{slash}BOOT") (class "Default")
      (node (ref "BOOT_BUTTON") (pin "3") (pinfunction "3_3") (pintype "passive"))
      (node (ref "BOOT_BUTTON") (pin "4") (pinfunction "4_4") (pintype "passive"))
      (node (ref "C6") (pin "1") (pinfunction "1_1") (pintype "passive"))
      (node (ref "R_BOOT") (pin "1") (pinfunction "1_1") (pintype "passive"))
      (node (ref "U2") (pin "15") (pinfunction "IO9_15") (pintype "bidirectional"))
    )
    (net (code "18") (name "IO{slash}CHANGE") (class "Default")
      (node (ref "C10") (pin "1") (pinfunction "1_1") (pintype "passive"))
      (node (ref "CHANGE_BUTTON") (pin "3") (pinfunction "3_3") (pintype "passive"))
      (node (ref "CHANGE_BUTTON") (pin "4") (pinfunction "4_4") (pintype "passive"))
      (node (ref "R_CHANGE") (pin "1") (pinfunction "1_1") (pintype "passive"))
      (node (ref "U2") (pin "23") (pinfunction "IO15_23") (pintype "bidirectional"))
    )
    (net (code "19") (name "MISO") (class "Default")
      (node (ref "D12") (pin "2") (pinfunction "2_2") (pintype "passive"))
      (node (ref "J4") (pin "P7") (pinfunction "DAT0_P7") (pintype "bidirectional"))
      (node (ref "R8") (pin "1") (pinfunction "1_1") (pintype "passive"))
      (node (ref "TP6_MISO") (pin "TP") (pinfunction "TP_TP") (pintype "input"))
      (node (ref "U1") (pin "2") (pinfunction "DO(IO1)_2") (pintype "bidirectional"))
      (node (ref "U2") (pin "27") (pinfunction "IO2_27") (pintype "bidirectional"))
    )
    (net (code "20") (name "MOSI") (class "Default")
      (node (ref "D11") (pin "2") (pinfunction "2_2") (pintype "passive"))
      (node (ref "J1") (pin "14") (pinfunction "14_14") (pintype "bidirectional"))
      (node (ref "J4") (pin "P3") (pinfunction "CMD_P3") (pintype "bidirectional"))
      (node (ref "R7") (pin "1") (pinfunction "1_1") (pintype "passive"))
      (node (ref "TP7_MOSI") (pin "TP") (pinfunction "TP_TP") (pintype "input"))
      (node (ref "U1") (pin "5") (pinfunction "DI(IO0)_5") (pintype "bidirectional"))
      (node (ref "U2") (pin "7") (pinfunction "IO7_7") (pintype "bidirectional"))
    )
    (net (code "21") (name "Net-(C5-Pad1)") (class "Default")
      (node (ref "C5") (pin "1") (pinfunction "1_1") (pintype "passive"))
      (node (ref "RESET_BUTTON") (pin "3") (pinfunction "3_3") (pintype "passive"))
      (node (ref "RESET_BUTTON") (pin "4") (pinfunction "4_4") (pintype "passive"))
      (node (ref "R_RESET") (pin "1") (pinfunction "1_1") (pintype "passive"))
    )
    (net (code "22") (name "Net-(CHG_LED-PadC)") (class "Default")
      (node (ref "CHG_LED") (pin "C") (pinfunction "C_C") (pintype "passive"))
      (node (ref "R1_BAT") (pin "1") (pinfunction "1_1") (pintype "passive"))
    )
    (net (code "23") (name "Net-(D2-CATHODE)") (class "Default")
      (node (ref "C1_BAT1") (pin "2") (pinfunction "2_2") (pintype "passive"))
      (node (ref "D2") (pin "1") (pinfunction "CATHODE_1") (pintype "bidirectional"))
      (node (ref "IC4") (pin "1") (pinfunction "VIN_1") (pintype "bidirectional"))
      (node (ref "IC4") (pin "3") (pinfunction "CE_3") (pintype "bidirectional"))
      (node (ref "Q1") (pin "2") (pinfunction "S_2") (pintype "bidirectional"))
    )
    (net (code "24") (name "Net-(D3-A)") (class "Default")
      (node (ref "C4") (pin "1") (pinfunction "1_1") (pintype "passive"))
      (node (ref "D3") (pin "2") (pinfunction "A_2") (pintype "bidirectional"))
      (node (ref "D4") (pin "1") (pinfunction "K_1") (pintype "bidirectional"))
    )
    (net (code "25") (name "Net-(D7-CATHODE)") (class "Default")
      (node (ref "D7") (pin "1") (pinfunction "CATHODE_1") (pintype "bidirectional"))
      (node (ref "R_CAPACITOR") (pin "1") (pinfunction "1_1") (pintype "passive"))
    )
    (net (code "26") (name "Net-(EPD_C1-Pad2)") (class "Default")
      (node (ref "EPD_C1") (pin "2") (pinfunction "2_2") (pintype "passive"))
      (node (ref "J1") (pin "4") (pinfunction "4_4") (pintype "bidirectional"))
    )
    (net (code "27") (name "Net-(EPD_C2-Pad2)") (class "Default")
      (node (ref "EPD_C2") (pin "2") (pinfunction "2_2") (pintype "passive"))
      (node (ref "J1") (pin "5") (pinfunction "5_5") (pintype "bidirectional"))
    )
    (net (code "28") (name "Net-(EPD_C6-Pad2)") (class "Default")
      (node (ref "EPD_C6") (pin "2") (pinfunction "2_2") (pintype "passive"))
      (node (ref "J1") (pin "18") (pinfunction "18_18") (pintype "bidirectional"))
    )
    (net (code "29") (name "Net-(EPD_C7-Pad2)") (class "Default")
      (node (ref "EPD_C7") (pin "2") (pinfunction "2_2") (pintype "passive"))
      (node (ref "J1") (pin "19") (pinfunction "19_19") (pintype "bidirectional"))
    )
    (net (code "30") (name "Net-(EPD_C8-Pad2)") (class "Default")
      (node (ref "EPD_C8") (pin "2") (pinfunction "2_2") (pintype "passive"))
      (node (ref "J1") (pin "20") (pinfunction "20_20") (pintype "bidirectional"))
    )
    (net (code "31") (name "Net-(EPD_C10-Pad2)") (class "Default")
      (node (ref "EPD_C10") (pin "2") (pinfunction "2_2") (pintype "passive"))
      (node (ref "J1") (pin "22") (pinfunction "22_22") (pintype "bidirectional"))
    )
    (net (code "32") (name "Net-(EPD_C12-Pad2)") (class "Default")
      (node (ref "EPD_C12") (pin "2") (pinfunction "2_2") (pintype "passive"))
      (node (ref "J1") (pin "24") (pinfunction "24_24") (pintype "bidirectional"))
    )
    (net (code "33") (name "Net-(IC1-CT)") (class "Default")
      (node (ref "C_DELAY") (pin "1") (pinfunction "1_1") (pintype "passive"))
      (node (ref "IC1") (pin "5") (pinfunction "CT_5") (pintype "bidirectional"))
    )
    (net (code "34") (name "Net-(J2-PadA5)") (class "Default")
      (node (ref "J2") (pin "A5") (pinfunction "A5_A5") (pintype "bidirectional"))
      (node (ref "R2-USB1") (pin "2") (pinfunction "2_2") (pintype "passive"))
    )
    (net (code "35") (name "Net-(J2-PadB5)") (class "Default")
      (node (ref "J2") (pin "B5") (pinfunction "B5_B5") (pintype "bidirectional"))
      (node (ref "R2-USB") (pin "1") (pinfunction "1_1") (pintype "passive"))
    )
    (net (code "36") (name "Net-(MCP73831-PROG)") (class "Default")
      (node (ref "MCP73831") (pin "5") (pinfunction "PROG_5") (pintype "input"))
      (node (ref "R2_BAT") (pin "2") (pinfunction "2_2") (pintype "passive"))
    )
    (net (code "37") (name "Net-(MCP73831-STAT)") (class "Default")
      (node (ref "MCP73831") (pin "1") (pinfunction "STAT_1") (pintype "output"))
      (node (ref "R1_BAT") (pin "2") (pinfunction "2_2") (pintype "passive"))
    )
    (net (code "38") (name "PREVGH") (class "Default")
      (node (ref "D5") (pin "1") (pinfunction "K_1") (pintype "bidirectional"))
      (node (ref "EPD_C9") (pin "2") (pinfunction "2_2") (pintype "passive"))
      (node (ref "J1") (pin "21") (pinfunction "21_21") (pintype "bidirectional"))
    )
    (net (code "39") (name "PREVGL") (class "Default")
      (node (ref "D4") (pin "2") (pinfunction "A_2") (pintype "bidirectional"))
      (node (ref "EPD_C11") (pin "2") (pinfunction "2_2") (pintype "passive"))
      (node (ref "J1") (pin "23") (pinfunction "23_23") (pintype "bidirectional"))
    )
    (net (code "40") (name "RESE") (class "Default")
      (node (ref "J1") (pin "3") (pinfunction "3_3") (pintype "bidirectional"))
      (node (ref "Q3") (pin "2") (pinfunction "S_2") (pintype "bidirectional"))
      (node (ref "R3") (pin "2") (pinfunction "2_2") (pintype "passive"))
    )
    (net (code "41") (name "RESE'") (class "Default")
      (node (ref "R2") (pin "2") (pinfunction "2_2") (pintype "passive"))
      (node (ref "R3") (pin "1") (pinfunction "1_1") (pintype "passive"))
      (node (ref "SJ1") (pin "2") (pinfunction "2_2") (pintype "passive"))
    )
    (net (code "42") (name "RESET") (class "Default")
      (node (ref "IC1") (pin "1") (pinfunction "VOUT_1") (pintype "bidirectional"))
      (node (ref "U2") (pin "3") (pinfunction "EN_3") (pintype "input"))
    )
    (net (code "43") (name "RTC_RST") (class "Default")
      (node (ref "U2") (pin "16") (pinfunction "IO18_16") (pintype "bidirectional"))
      (node (ref "U3") (pin "4") (pinfunction "~{RST}_4") (pintype "input"))
    )
    (net (code "44") (name "RX") (class "Default")
      (node (ref "TP2_RX") (pin "TP") (pinfunction "TP_TP") (pintype "input"))
      (node (ref "U2") (pin "24") (pinfunction "RXD0/GPIO17_24") (pintype "bidirectional"))
    )
    (net (code "45") (name "SCK") (class "Default")
      (node (ref "D10") (pin "2") (pinfunction "2_2") (pintype "passive"))
      (node (ref "J1") (pin "13") (pinfunction "13_13") (pintype "bidirectional"))
      (node (ref "J4") (pin "P5") (pinfunction "CLK_P5") (pintype "bidirectional"))
      (node (ref "R6") (pin "1") (pinfunction "1_1") (pintype "passive"))
      (node (ref "TP8_SCK") (pin "TP") (pinfunction "TP_TP") (pintype "input"))
      (node (ref "U1") (pin "6") (pinfunction "CLK_6") (pintype "input"))
      (node (ref "U2") (pin "6") (pinfunction "IO6_6") (pintype "bidirectional"))
    )
    (net (code "46") (name "SCL") (class "Default")
      (node (ref "J3") (pin "4") (pinfunction "4_4") (pintype "passive"))
      (node (ref "R2_PINH") (pin "1") (pinfunction "1_1") (pintype "passive"))
      (node (ref "SENSOR2") (pin "4") (pinfunction "SCK_4") (pintype "input"))
      (node (ref "U2") (pin "20") (pinfunction "IO22_20") (pintype "bidirectional"))
      (node (ref "U3") (pin "16") (pinfunction "SCL_16") (pintype "input"))
      (node (ref "U4") (pin "7") (pinfunction "SCL_7") (pintype "input"))
    )
    (net (code "47") (name "SDA") (class "Default")
      (node (ref "J3") (pin "3") (pinfunction "3_3") (pintype "passive"))
      (node (ref "R1_PINH") (pin "1") (pinfunction "1_1") (pintype "passive"))
      (node (ref "SENSOR2") (pin "3") (pinfunction "SDI_3") (pintype "bidirectional"))
      (node (ref "U2") (pin "19") (pinfunction "IO21_19") (pintype "bidirectional"))
      (node (ref "U3") (pin "15") (pinfunction "SDA_15") (pintype "bidirectional"))
      (node (ref "U4") (pin "8") (pinfunction "SDA_8") (pintype "bidirectional"))
    )
    (net (code "48") (name "SRC") (class "Default")
      (node (ref "C4") (pin "2") (pinfunction "2_2") (pintype "passive"))
      (node (ref "D5") (pin "2") (pinfunction "A_2") (pintype "bidirectional"))
      (node (ref "L1") (pin "1") (pinfunction "1_1") (pintype "passive"))
      (node (ref "Q3") (pin "3") (pinfunction "D_3") (pintype "bidirectional"))
    )
    (net (code "49") (name "SS_SD") (class "Default")
      (node (ref "D8") (pin "2") (pinfunction "2_2") (pintype "passive"))
      (node (ref "J4") (pin "P2") (pinfunction "CD/DAT3_P2") (pintype "bidirectional"))
      (node (ref "R10") (pin "1") (pinfunction "1_1") (pintype "passive"))
      (node (ref "U2") (pin "4") (pinfunction "IO4_4") (pintype "bidirectional"))
    )
    (net (code "50") (name "TX") (class "Default")
      (node (ref "TP1_TX") (pin "TP") (pinfunction "TP_TP") (pintype "input"))
      (node (ref "U2") (pin "25") (pinfunction "TXD0/GPIO16_25") (pintype "bidirectional"))
    )
    (net (code "51") (name "USB_D+") (class "Default")
      (node (ref "D1") (pin "1") (pinfunction "I/O1_1_1") (pintype "bidirectional"))
      (node (ref "U2") (pin "14") (pinfunction "IO13_14") (pintype "bidirectional"))
    )
    (net (code "52") (name "USB_D-") (class "Default")
      (node (ref "D1") (pin "3") (pinfunction "I/O2_1_3") (pintype "bidirectional"))
      (node (ref "U2") (pin "13") (pinfunction "IO12_13") (pintype "bidirectional"))
    )
    (net (code "53") (name "VBAT") (class "Default")
      (node (ref "C2_BAT") (pin "1") (pinfunction "1_1") (pintype "passive"))
      (node (ref "MCP73831") (pin "3") (pinfunction "VBAT_3") (pintype "power_in"))
      (node (ref "Q1") (pin "3") (pinfunction "D_3") (pintype "bidirectional"))
      (node (ref "TP3_VBAT") (pin "TP") (pinfunction "TP_TP") (pintype "input"))
      (node (ref "U4") (pin "2") (pinfunction "CELL_2") (pintype "power_in"))
      (node (ref "U4") (pin "3") (pinfunction "VDD_3") (pintype "power_in"))
    )
    (net (code "54") (name "VBUS") (class "Default")
      (node (ref "C1_BAT") (pin "1") (pinfunction "1_1") (pintype "passive"))
      (node (ref "C4_USB") (pin "1") (pinfunction "1_1") (pintype "passive"))
      (node (ref "C5_USB") (pin "1") (pinfunction "1_1") (pintype "passive"))
      (node (ref "CHG_LED") (pin "A") (pinfunction "A_A") (pintype "passive"))
      (node (ref "D1") (pin "5") (pinfunction "VBUS_5") (pintype "bidirectional"))
      (node (ref "D2") (pin "2") (pinfunction "ANODE_2") (pintype "bidirectional"))
      (node (ref "MCP73831") (pin "4") (pinfunction "VIN_4") (pintype "power_in"))
      (node (ref "PFMF.050.1") (pin "2") (pinfunction "2_2") (pintype "passive"))
      (node (ref "Q1") (pin "1") (pinfunction "G_1") (pintype "bidirectional"))
      (node (ref "R1_PWRUSB") (pin "2") (pinfunction "2_2") (pintype "passive"))
      (node (ref "TP1_VBUS") (pin "TP") (pinfunction "TP_TP") (pintype "input"))
    )
    (net (code "55") (name "VRTC") (class "Default")
      (node (ref "C10_SUPERCAP") (pin "2") (pinfunction "2_2") (pintype "passive"))
      (node (ref "C8") (pin "1") (pinfunction "1_1") (pintype "passive"))
      (node (ref "R_CAPACITOR") (pin "2") (pinfunction "2_2") (pintype "passive"))
      (node (ref "U3") (pin "14") (pinfunction "VBAT_14") (pintype "power_in"))
    )
    (net (code "56") (name "VUSB") (class "Default")
      (node (ref "J2") (pin "A4") (pinfunction "A4_A4") (pintype "bidirectional"))
      (node (ref "J2") (pin "A9") (pinfunction "A9_A9") (pintype "bidirectional"))
      (node (ref "J2") (pin "B4") (pinfunction "B4_B4") (pintype "bidirectional"))
      (node (ref "J2") (pin "B9") (pinfunction "B9_B9") (pintype "bidirectional"))
      (node (ref "PFMF.050.1") (pin "1") (pinfunction "1_1") (pintype "passive"))
    )
    (net (code "57") (name "unconnected-(IC1-NC-Pad4)") (class "Default")
      (node (ref "IC1") (pin "4") (pinfunction "NC_4") (pintype "no_connect"))
    )
    (net (code "58") (name "unconnected-(IC4-NC-Pad4)") (class "Default")
      (node (ref "IC4") (pin "4") (pinfunction "NC_4") (pintype "no_connect"))
    )
    (net (code "59") (name "unconnected-(J1-Pad1)") (class "Default")
      (node (ref "J1") (pin "1") (pinfunction "1_1") (pintype "bidirectional"))
    )
    (net (code "60") (name "unconnected-(J1-Pad6)") (class "Default")
      (node (ref "J1") (pin "6") (pinfunction "6_6") (pintype "bidirectional"))
    )
    (net (code "61") (name "unconnected-(J1-Pad7)") (class "Default")
      (node (ref "J1") (pin "7") (pinfunction "7_7") (pintype "bidirectional"))
    )
    (net (code "62") (name "unconnected-(J2-PadA8)") (class "Default")
      (node (ref "J2") (pin "A8") (pinfunction "A8_A8") (pintype "bidirectional"))
    )
    (net (code "63") (name "unconnected-(J2-PadB8)") (class "Default")
      (node (ref "J2") (pin "B8") (pinfunction "B8_B8") (pintype "bidirectional"))
    )
    (net (code "64") (name "unconnected-(J4-DAT1-PadP8)") (class "Default")
      (node (ref "J4") (pin "P8") (pinfunction "DAT1_P8") (pintype "bidirectional"))
    )
    (net (code "65") (name "unconnected-(J4-DAT2-PadP1)") (class "Default")
      (node (ref "J4") (pin "P1") (pinfunction "DAT2_P1") (pintype "bidirectional"))
    )
    (net (code "66") (name "unconnected-(J4-DETECTION_1-PadS1)") (class "Default")
      (node (ref "J4") (pin "S1") (pinfunction "DETECTION_1_S1") (pintype "bidirectional"))
    )
    (net (code "67") (name "unconnected-(J4-DETECTION_2-PadS2)") (class "Default")
      (node (ref "J4") (pin "S2") (pinfunction "DETECTION_2_S2") (pintype "bidirectional"))
    )
    (net (code "68") (name "unconnected-(U2-NC-Pad22)") (class "Default")
      (node (ref "U2") (pin "22") (pinfunction "NC_22") (pintype "no_connect"))
    )
    (net (code "69") (name "unconnected-(U4-~{ALERT}-Pad5)") (class "Default")
      (node (ref "U4") (pin "5") (pinfunction "~{ALERT}_5") (pintype "output"))
    )
  )
)
